# led_board.net
KiCad netlist of a schematic drawn in EAGLE
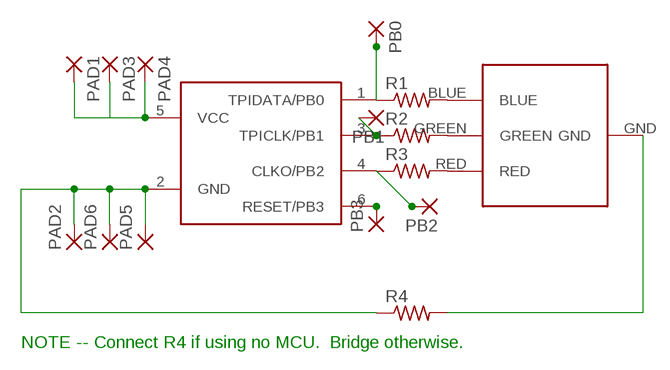
[diagram p0: schematic, sheet 1]

(export (version "E")
  (design (tool "Eeschema 10.0.6"))
  (components
    (comp (ref "PAD1")
      (value "1,6/0,8")
      (footprint "eagle-import:1,6_0,8")
      (libsource (lib "eagle-import") (part "1,6/0,8"))
    )
    (comp (ref "PAD2")
      (value "1,6/0,8")
      (footprint "eagle-import:1,6_0,8")
      (libsource (lib "eagle-import") (part "1,6/0,8"))
    )
    (comp (ref "PAD3")
      (value "1,6/0,8")
      (footprint "eagle-import:1,6_0,8")
      (libsource (lib "eagle-import") (part "1,6/0,8"))
    )
    (comp (ref "PAD4")
      (value "1,6/0,8")
      (footprint "eagle-import:1,6_0,8")
      (libsource (lib "eagle-import") (part "1,6/0,8"))
    )
    (comp (ref "PAD5")
      (value "1,6/0,8")
      (footprint "eagle-import:1,6_0,8")
      (libsource (lib "eagle-import") (part "1,6/0,8"))
    )
    (comp (ref "PAD6")
      (value "1,6/0,8")
      (footprint "eagle-import:1,6_0,8")
      (libsource (lib "eagle-import") (part "1,6/0,8"))
    )
    (comp (ref "PB0")
      (value "1,6/0,8")
      (footprint "eagle-import:1,6_0,8")
      (libsource (lib "eagle-import") (part "1,6/0,8"))
    )
    (comp (ref "PB1")
      (value "1,6/0,8")
      (footprint "eagle-import:1,6_0,8")
      (libsource (lib "eagle-import") (part "1,6/0,8"))
    )
    (comp (ref "PB2")
      (value "1,6/0,8")
      (footprint "eagle-import:1,6_0,8")
      (libsource (lib "eagle-import") (part "1,6/0,8"))
    )
    (comp (ref "PB3")
      (value "1,6/0,8")
      (footprint "eagle-import:1,6_0,8")
      (libsource (lib "eagle-import") (part "1,6/0,8"))
    )
    (comp (ref "R1")
      (value "R-US_M1206")
      (footprint "eagle-import:M1206")
      (libsource (lib "eagle-import") (part "R-US_M1206"))
    )
    (comp (ref "R2")
      (value "R-US_M1206")
      (footprint "eagle-import:M1206")
      (libsource (lib "eagle-import") (part "R-US_M1206"))
    )
    (comp (ref "R3")
      (value "R-US_M1206")
      (footprint "eagle-import:M1206")
      (libsource (lib "eagle-import") (part "R-US_M1206"))
    )
    (comp (ref "R4")
      (value "R-US_M1206")
      (footprint "eagle-import:M1206")
      (libsource (lib "eagle-import") (part "R-US_M1206"))
    )
    (comp (ref "U$1")
      (value "BIVAR-RGB-LED")
      (footprint "eagle-import:7.6X7.6MM-LED")
      (libsource (lib "eagle-import") (part "BIVAR-RGB-LED"))
    )
    (comp (ref "U$2")
      (value "ATTINY10SOT")
      (footprint "eagle-import:SOT23-6")
      (libsource (lib "eagle-import") (part "ATTINY10SOT"))
    )
  )
  (nets
    (net (code "1") (name "Net-(PAD1-P)") (class "Default")
      (node (ref "PAD1") (pin "1") (pinfunction "P_1") (pintype "passive"))
      (node (ref "PAD3") (pin "1") (pinfunction "P_1") (pintype "passive"))
      (node (ref "PAD4") (pin "1") (pinfunction "P_1") (pintype "passive"))
      (node (ref "U$2") (pin "5") (pinfunction "VCC_5") (pintype "bidirectional"))
    )
    (net (code "2") (name "Net-(PAD2-P)") (class "Default")
      (node (ref "PAD2") (pin "1") (pinfunction "P_1") (pintype "passive"))
      (node (ref "PAD5") (pin "1") (pinfunction "P_1") (pintype "passive"))
      (node (ref "PAD6") (pin "1") (pinfunction "P_1") (pintype "passive"))
      (node (ref "R4") (pin "1") (pinfunction "1_1") (pintype "passive"))
      (node (ref "U$2") (pin "2") (pinfunction "GND_2") (pintype "bidirectional"))
    )
    (net (code "3") (name "Net-(PB0-P)") (class "Default")
      (node (ref "PB0") (pin "1") (pinfunction "P_1") (pintype "passive"))
      (node (ref "R1") (pin "1") (pinfunction "1_1") (pintype "passive"))
      (node (ref "U$2") (pin "1") (pinfunction "TPIDATA/PB0_1") (pintype "bidirectional"))
    )
    (net (code "4") (name "Net-(PB1-P)") (class "Default")
      (node (ref "PB1") (pin "1") (pinfunction "P_1") (pintype "passive"))
      (node (ref "R2") (pin "1") (pinfunction "1_1") (pintype "passive"))
      (node (ref "U$2") (pin "3") (pinfunction "TPICLK/PB1_3") (pintype "bidirectional"))
    )
    (net (code "5") (name "Net-(PB2-P)") (class "Default")
      (node (ref "PB2") (pin "1") (pinfunction "P_1") (pintype "passive"))
      (node (ref "R3") (pin "1") (pinfunction "1_1") (pintype "passive"))
      (node (ref "U$2") (pin "4") (pinfunction "CLKO/PB2_4") (pintype "bidirectional"))
    )
    (net (code "6") (name "Net-(PB3-P)") (class "Default")
      (node (ref "PB3") (pin "1") (pinfunction "P_1") (pintype "passive"))
      (node (ref "U$2") (pin "6") (pinfunction "RESET/PB3_6") (pintype "bidirectional"))
    )
    (net (code "7") (name "Net-(R1-Pad2)") (class "Default")
      (node (ref "R1") (pin "2") (pinfunction "2_2") (pintype "passive"))
      (node (ref "U$1") (pin "BLUE") (pinfunction "BLUE_BLUE") (pintype "bidirectional"))
    )
    (net (code "8") (name "Net-(R2-Pad2)") (class "Default")
      (node (ref "R2") (pin "2") (pinfunction "2_2") (pintype "passive"))
      (node (ref "U$1") (pin "GREEN") (pinfunction "GREEN_GREEN") (pintype "bidirectional"))
    )
    (net (code "9") (name "Net-(R3-Pad2)") (class "Default")
      (node (ref "R3") (pin "2") (pinfunction "2_2") (pintype "passive"))
      (node (ref "U$1") (pin "RED") (pinfunction "RED_RED") (pintype "bidirectional"))
    )
    (net (code "10") (name "Net-(R4-Pad2)") (class "Default")
      (node (ref "R4") (pin "2") (pinfunction "2_2") (pintype "passive"))
      (node (ref "U$1") (pin "GND") (pinfunction "GND_GND") (pintype "bidirectional"))
    )
  )
)
